# IMU_Radio.net
KiCad netlist of a schematic drawn in Altium Designer
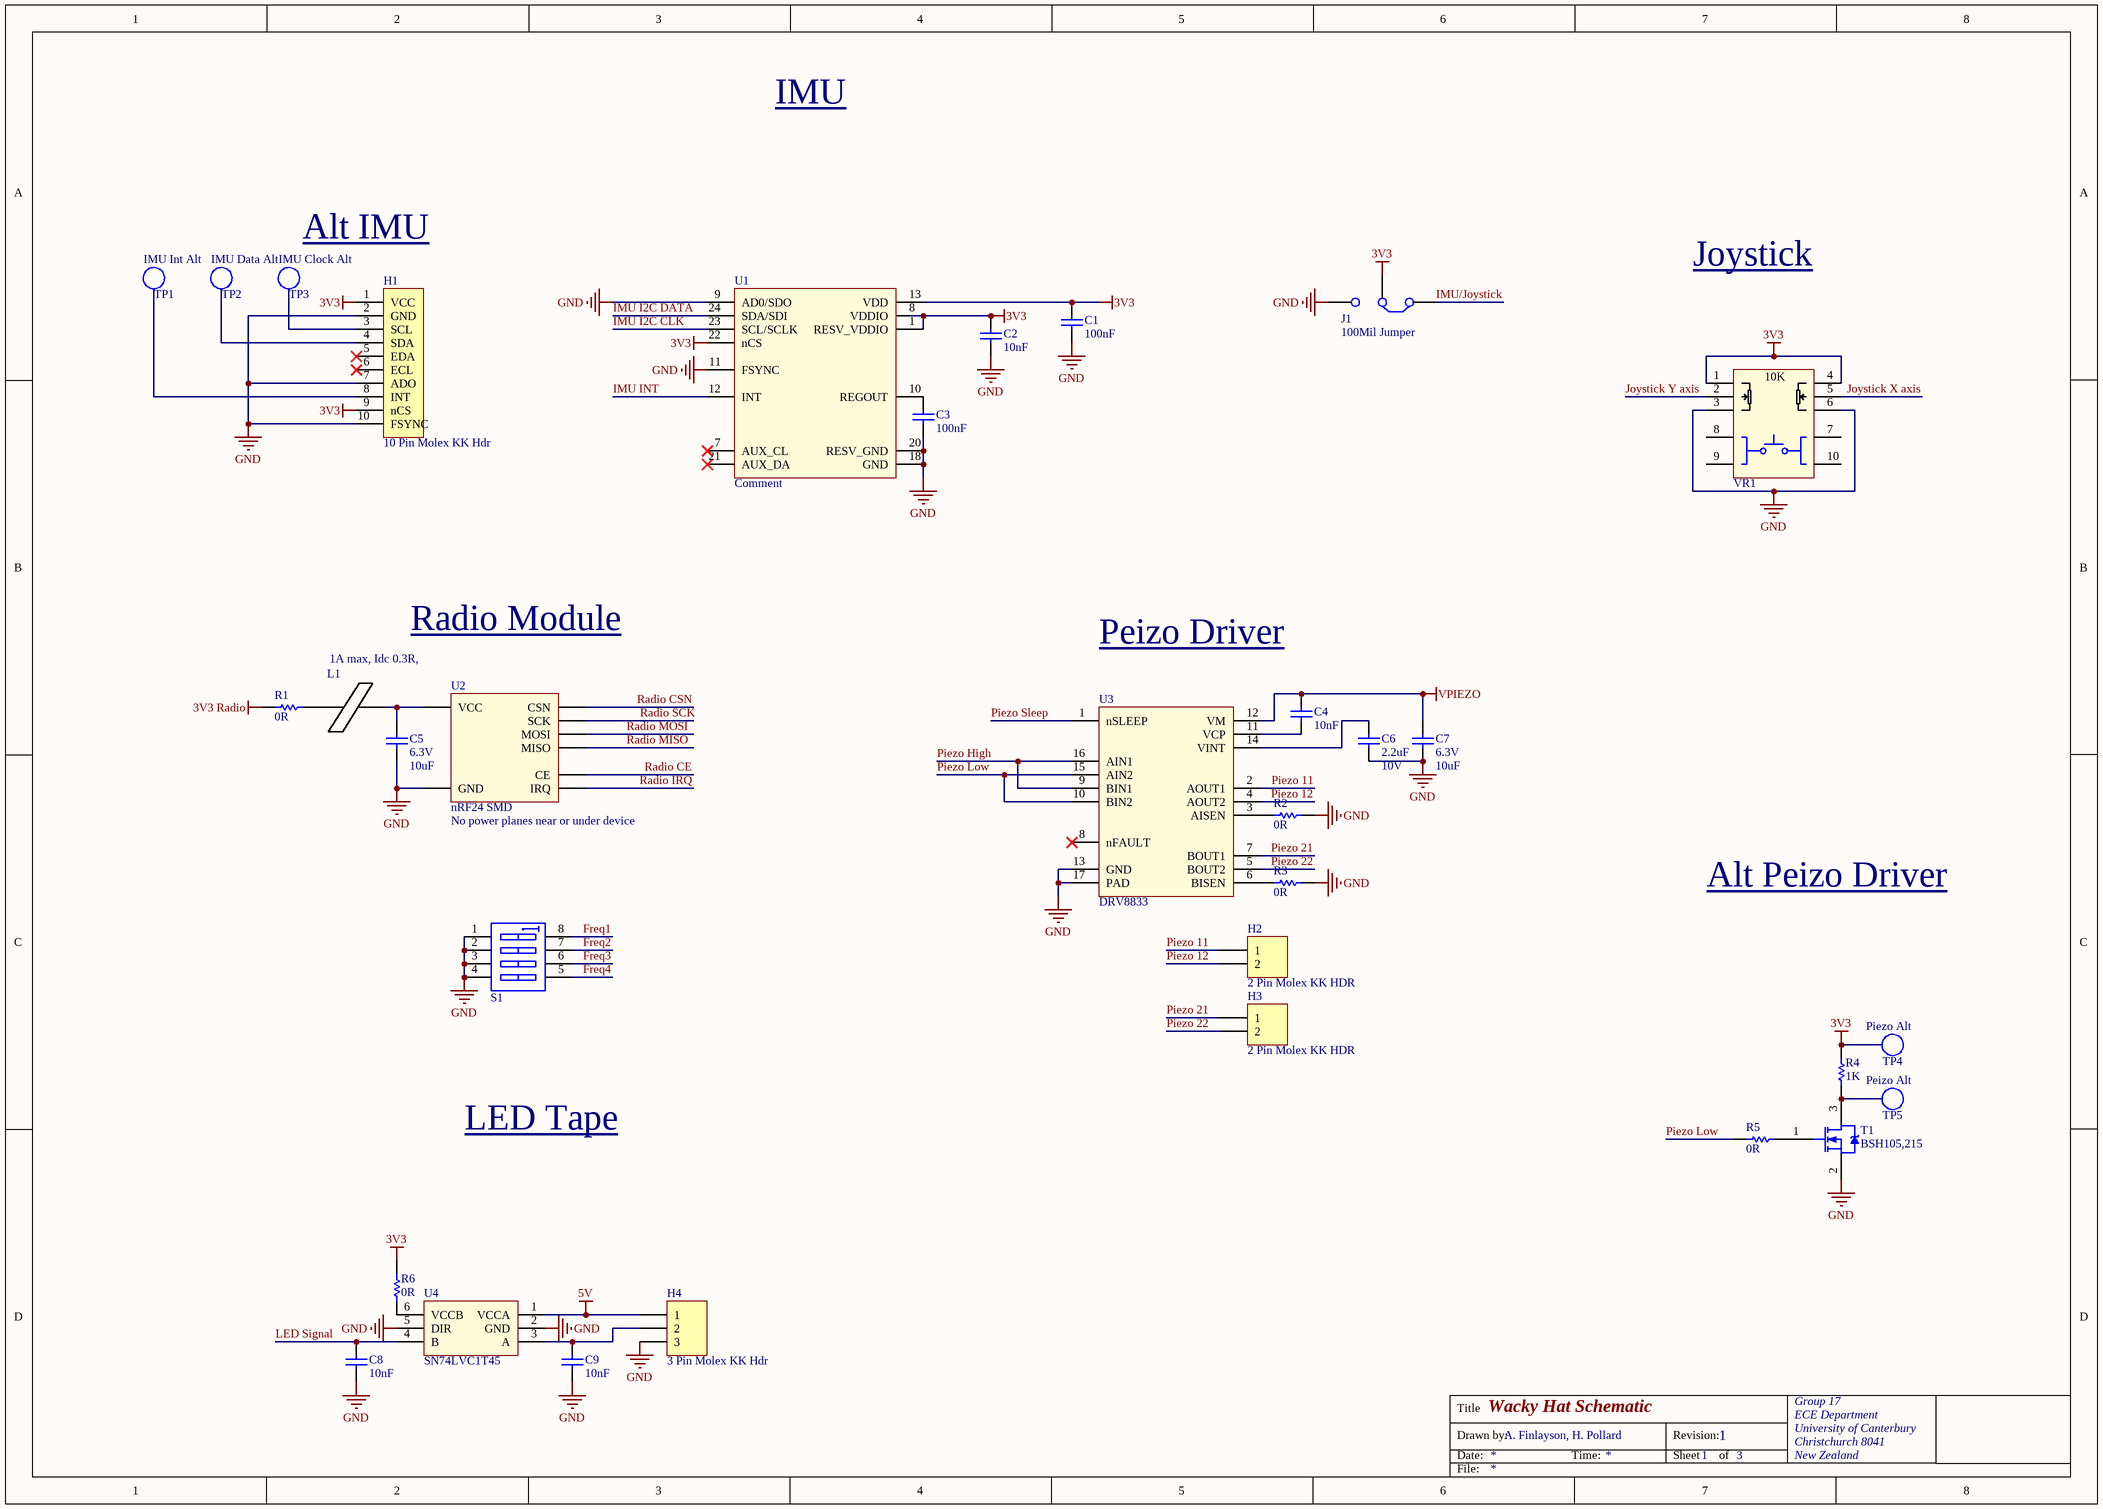
[diagram p0: IMU_Radio.SchDoc]

(export (version "E")
  (design (tool "Eeschema 10.0.6"))
  (components
    (comp (ref "C1")
      (value "100nF")
      (footprint "CAPC1608L")
      (description "CAP CER 100nF X7R +-10% 50V 0603")
      (libsource (lib "ECE AD19Components_19V1") (part "CC_100nF_0603"))
    )
    (comp (ref "C2")
      (value "10nF")
      (footprint "CAPC1608L")
      (description "CAP CER 10nF X7R +-10% 50V 0603")
      (libsource (lib "ECE AD19Components_19V1") (part "CC_10nF_0603"))
    )
    (comp (ref "C3")
      (value "100nF")
      (footprint "CAPC1608L")
      (description "CAP CER 100nF X7R +-10% 50V 0603")
      (libsource (lib "ECE AD19Components_19V1") (part "CC_100nF_0603"))
    )
    (comp (ref "C4")
      (value "10nF")
      (footprint "CAPC1608L")
      (description "CAP CER 10nF X7R +-10% 50V 0603")
      (libsource (lib "ECE AD19Components_19V1") (part "CC_10nF_0603"))
    )
    (comp (ref "C5")
      (value "10uF")
      (footprint "CAPC1608L")
      (description "CAP CER 10UF X5R +-20% 6V3 0603")
      (fields (field (name "VOLTAGE - RATED") "6.3V"))
      (libsource (lib "ECE AD19Components_19V1") (part "CC_10uF_0603"))
    )
    (comp (ref "C6")
      (value "2.2uF")
      (footprint "CAPC1608L")
      (description "CAP CER 2.2uF X5R +-20% 10V 0603")
      (fields (field (name "MAX VOLTAGE") "10V"))
      (libsource (lib "ECE AD19Components_19V1") (part "CC_2.2uF_0603"))
    )
    (comp (ref "C7")
      (value "10uF")
      (footprint "CAPC1608L")
      (description "CAP CER 10UF X5R +-20% 6V3 0603")
      (fields (field (name "VOLTAGE - RATED") "6.3V"))
      (libsource (lib "ECE AD19Components_19V1") (part "CC_10uF_0603"))
    )
    (comp (ref "C8")
      (value "10nF")
      (footprint "CAPC1608L")
      (description "CAP CER 10nF X7R +-10% 50V 0603")
      (libsource (lib "ECE AD19Components_19V1") (part "CC_10nF_0603"))
    )
    (comp (ref "C9")
      (value "10nF")
      (footprint "CAPC1608L")
      (description "CAP CER 10nF X7R +-10% 50V 0603")
      (libsource (lib "ECE AD19Components_19V1") (part "CC_10nF_0603"))
    )
    (comp (ref "H1")
      (value "10 Pin Molex KK Hdr")
      (footprint "MOLEX_KK_10_HDR")
      (description "CONN HEADER 10POS 2.54mm VERT_ Thru Hole")
      (libsource (lib "ECE AD19Components_19V1") (part "JA_MOLEX_KK_10POS"))
    )
    (comp (ref "H2")
      (value "2 Pin Molex KK HDR")
      (footprint "MOLEX_KK_2_HDR")
      (description "CONN HEADER 2POS 2.54mm VERT_Thru Hole")
      (libsource (lib "ECE AD19Components_19V1") (part "JA_MOLEX_KK_2POS"))
    )
    (comp (ref "H3")
      (value "2 Pin Molex KK HDR")
      (footprint "MOLEX_KK_2_HDR")
      (description "CONN HEADER 2POS 2.54mm VERT_Thru Hole")
      (libsource (lib "ECE AD19Components_19V1") (part "JA_MOLEX_KK_2POS"))
    )
    (comp (ref "H4")
      (value "3 Pin Molex KK Hdr")
      (footprint "MOLEX_KK_3_HDR")
      (description "CONN HEADER 3POS 2.54mm VERT_Thru Hole")
      (fields (field (name "MANUFACTURER") "Molex"))
      (libsource (lib "ECE AD19Components_19V1") (part "JA_MOLEX_KK_3POS"))
    )
    (comp (ref "J1")
      (value "100Mil Jumper")
      (footprint "JMP2.54-CO")
      (description "2.54mm Jumper change over, Thru Hole")
      (libsource (lib "ECE AD19Components_19V1") (part "TP_JUMPER_CO"))
    )
    (comp (ref "L1")
      (value "1A max, Idc 0.3R,")
      (footprint "INDC3216L")
      (description "Ferrite Bead, Rdc 0.3R, Z100MHZ 600R, Imax 1A, SMD 1206")
      (fields
        (field (name "MANUFACTURER") "FAIR-RITE")
        (field (name "MANUFACTURER PART NUMBER") "2512066017Y1")
      )
      (libsource (lib "ECE AD19Components_19V1") (part "IN_Ferrite-Bead"))
    )
    (comp (ref "R1")
      (value "0R")
      (footprint "RESC1608L")
      (description "RES 0.0 OHM 1/10W 5% 0603 SMD")
      (libsource (lib "ECE AD19Components_19V1") (part "RS_0R0"))
    )
    (comp (ref "R2")
      (value "0R")
      (footprint "RESC1608L")
      (description "RES 0.0 OHM 1/10W 5% 0603 SMD")
      (libsource (lib "ECE AD19Components_19V1") (part "RS_0R0"))
    )
    (comp (ref "R3")
      (value "0R")
      (footprint "RESC1608L")
      (description "RES 0.0 OHM 1/10W 5% 0603 SMD")
      (libsource (lib "ECE AD19Components_19V1") (part "RS_0R0"))
    )
    (comp (ref "R4")
      (value "1K")
      (footprint "RESC1608L")
      (description "RES 1.0K OHM 1/10W 5% 0603 SMD")
      (libsource (lib "ECE AD19Components_19V1") (part "RS_1K"))
    )
    (comp (ref "R5")
      (value "0R")
      (footprint "RESC1608L")
      (description "RES 0.0 OHM 1/10W 5% 0603 SMD")
      (libsource (lib "ECE AD19Components_19V1") (part "RS_0R0"))
    )
    (comp (ref "R6")
      (value "0R")
      (footprint "RESC1608L")
      (description "RES 0.0 OHM 1/10W 5% 0603 SMD")
      (libsource (lib "ECE AD19Components_19V1") (part "RS_0R0"))
    )
    (comp (ref "S1")
      (value "WS_SW DIP-4")
      (footprint "DIP_SW_4WAY_SMD -")
      (description "DIP Switch, 4 Position, SPST SMD")
      (fields
        (field (name "MANUFACTURER") "OMRON ELECTRONIC COMPONENTS")
        (field (name "MANUFACTURER PART NUMBER") "A6SN-4101")
      )
      (libsource (lib "ECE AD19Components_19V1") (part "WS_SW DIP-4"))
    )
    (comp (ref "T1")
      (value "BSH105,215")
      (footprint "SOT23_L")
      (description "MOSFET N-CH 20V 1.05A SOT-23")
      (fields
        (field (name "MANUFACTURER") "NXP Semiconductors")
        (field (name "MANUFACTURER PART NUMBER") "BSH105,215")
      )
      (libsource (lib "ECE AD19Components_19V1") (part "TM_BSH105"))
    )
    (comp (ref "TP1")
      (value "IMU Int Alt")
      (footprint "TP_0603")
      (description "Test Point 1.65X0.9X1.2mm SMD")
      (fields
        (field (name "MANUFACTURER") "TE Connectivity AMP Connectors")
        (field (name "MANUFACTURER PART NUMBER") "1625854-3")
      )
      (libsource (lib "ECE AD19Components_19V1") (part "TP_0603"))
    )
    (comp (ref "TP2")
      (value "IMU Data Alt")
      (footprint "TP_0603")
      (description "Test Point 1.65X0.9X1.2mm SMD")
      (fields
        (field (name "MANUFACTURER") "TE Connectivity AMP Connectors")
        (field (name "MANUFACTURER PART NUMBER") "1625854-3")
      )
      (libsource (lib "ECE AD19Components_19V1") (part "TP_0603"))
    )
    (comp (ref "TP3")
      (value "IMU Clock Alt")
      (footprint "TP_0603")
      (description "Test Point 1.65X0.9X1.2mm SMD")
      (fields
        (field (name "MANUFACTURER") "TE Connectivity AMP Connectors")
        (field (name "MANUFACTURER PART NUMBER") "1625854-3")
      )
      (libsource (lib "ECE AD19Components_19V1") (part "TP_0603"))
    )
    (comp (ref "TP4")
      (value "Piezo Alt")
      (footprint "TP_0603")
      (description "Test Point 1.65X0.9X1.2mm SMD")
      (fields
        (field (name "MANUFACTURER") "TE Connectivity AMP Connectors")
        (field (name "MANUFACTURER PART NUMBER") "1625854-3")
      )
      (libsource (lib "ECE AD19Components_19V1") (part "TP_0603"))
    )
    (comp (ref "TP5")
      (value "Peizo Alt")
      (footprint "TP_0603")
      (description "Test Point 1.65X0.9X1.2mm SMD")
      (fields
        (field (name "MANUFACTURER") "TE Connectivity AMP Connectors")
        (field (name "MANUFACTURER PART NUMBER") "1625854-3")
      )
      (libsource (lib "ECE AD19Components_19V1") (part "TP_0603"))
    )
    (comp (ref "U1")
      (value "Comment")
      (footprint "Quad24")
      (description "9 axis IMU")
      (libsource (lib "ENCE461AD19_19V2") (part "MPU-9250"))
    )
    (comp (ref "U2")
      (value "nRF24 SMD")
      (footprint "NRF24")
      (description "nRF24 SMD Module")
      (fields (field (name "WARNING") "No power planes near or under device"))
      (libsource (lib "ENCE461AD19_19V2") (part "NRF24"))
    )
    (comp (ref "U3")
      (value "DRV8833")
      (footprint "HTSOP16")
      (description "Dual H-Bridge Motor Driver 1.5A")
      (libsource (lib "ENCE461AD19_19V2") (part "DRV8833"))
    )
    (comp (ref "U4")
      (value "SN74LVC1T45")
      (footprint "SOT23-6_N")
      (description "1.8V - 5V level converter")
      (libsource (lib "ENCE461_extras_2020") (part "SN74LVC1T45"))
    )
    (comp (ref "VR1")
      (value "Joystick 10k with Sw")
      (footprint "Joystick_Sw")
      (description "JOYSTICK 10K OHM 2 AXIS TH")
      (libsource (lib "ENCE461AD19_19V2") (part "Joystick 10k with Sw"))
    )
  )
  (nets
    (net (code "1") (name "/Freq1") (class "Default")
      (node (ref "S1") (pin "8") (pinfunction "B1_8") (pintype "passive"))
    )
    (net (code "2") (name "/Freq2") (class "Default")
      (node (ref "S1") (pin "7") (pinfunction "B2_7") (pintype "passive"))
    )
    (net (code "3") (name "/Freq3") (class "Default")
      (node (ref "S1") (pin "6") (pinfunction "B3_6") (pintype "passive"))
    )
    (net (code "4") (name "/Freq4") (class "Default")
      (node (ref "S1") (pin "5") (pinfunction "B4_5") (pintype "passive"))
    )
    (net (code "5") (name "/IMU I2C CLK") (class "Default")
      (node (ref "U1") (pin "23") (pinfunction "SCL/SCLK_23") (pintype "passive"))
    )
    (net (code "6") (name "/IMU I2C DATA") (class "Default")
      (node (ref "U1") (pin "24") (pinfunction "SDA/SDI_24") (pintype "passive"))
    )
    (net (code "7") (name "/IMU INT") (class "Default")
      (node (ref "U1") (pin "12") (pinfunction "INT_12") (pintype "passive"))
    )
    (net (code "8") (name "/IMU{slash}Joystick") (class "Default")
      (node (ref "J1") (pin "1") (pinfunction "C1_1") (pintype "passive"))
    )
    (net (code "9") (name "/Joystick X axis") (class "Default")
      (node (ref "VR1") (pin "5") (pinfunction "2'_5") (pintype "passive"))
    )
    (net (code "10") (name "/Joystick Y axis") (class "Default")
      (node (ref "VR1") (pin "2") (pinfunction "2_2") (pintype "passive"))
    )
    (net (code "11") (name "/LED Signal") (class "Default")
      (node (ref "C8") (pin "2") (pinfunction "2_2") (pintype "passive"))
      (node (ref "U4") (pin "4") (pinfunction "B_4") (pintype "passive"))
    )
    (net (code "12") (name "/Piezo 11") (class "Default")
      (node (ref "H2") (pin "1") (pinfunction "1_1") (pintype "passive"))
      (node (ref "U3") (pin "2") (pinfunction "AOUT1_2") (pintype "passive"))
    )
    (net (code "13") (name "/Piezo 12") (class "Default")
      (node (ref "H2") (pin "2") (pinfunction "2_2") (pintype "passive"))
      (node (ref "U3") (pin "4") (pinfunction "AOUT2_4") (pintype "passive"))
    )
    (net (code "14") (name "/Piezo 21") (class "Default")
      (node (ref "H3") (pin "1") (pinfunction "1_1") (pintype "passive"))
      (node (ref "U3") (pin "7") (pinfunction "BOUT1_7") (pintype "passive"))
    )
    (net (code "15") (name "/Piezo 22") (class "Default")
      (node (ref "H3") (pin "2") (pinfunction "2_2") (pintype "passive"))
      (node (ref "U3") (pin "5") (pinfunction "BOUT2_5") (pintype "passive"))
    )
    (net (code "16") (name "/Piezo High") (class "Default")
      (node (ref "U3") (pin "16") (pinfunction "AIN1_16") (pintype "passive"))
      (node (ref "U3") (pin "9") (pinfunction "BIN1_9") (pintype "passive"))
    )
    (net (code "17") (name "/Piezo Low") (class "Default")
      (node (ref "R5") (pin "1") (pinfunction "1_1") (pintype "passive"))
      (node (ref "U3") (pin "10") (pinfunction "BIN2_10") (pintype "passive"))
      (node (ref "U3") (pin "15") (pinfunction "AIN2_15") (pintype "passive"))
    )
    (net (code "18") (name "/Piezo Sleep") (class "Default")
      (node (ref "U3") (pin "1") (pinfunction "nSLEEP_1") (pintype "passive"))
    )
    (net (code "19") (name "/Radio CE") (class "Default")
      (node (ref "U2") (pin "3") (pinfunction "CE_3") (pintype "passive"))
    )
    (net (code "20") (name "/Radio CSN") (class "Default")
      (node (ref "U2") (pin "4") (pinfunction "CSN_4") (pintype "passive"))
    )
    (net (code "21") (name "/Radio IRQ") (class "Default")
      (node (ref "U2") (pin "8") (pinfunction "IRQ_8") (pintype "passive"))
    )
    (net (code "22") (name "/Radio MISO") (class "Default")
      (node (ref "U2") (pin "7") (pinfunction "MISO_7") (pintype "passive"))
    )
    (net (code "23") (name "/Radio MOSI") (class "Default")
      (node (ref "U2") (pin "6") (pinfunction "MOSI_6") (pintype "passive"))
    )
    (net (code "24") (name "/Radio SCK") (class "Default")
      (node (ref "U2") (pin "5") (pinfunction "SCK_5") (pintype "passive"))
    )
    (net (code "25") (name "3V3") (class "Default")
      (node (ref "C1") (pin "2") (pinfunction "2_2") (pintype "passive"))
      (node (ref "C2") (pin "2") (pinfunction "2_2") (pintype "passive"))
      (node (ref "H1") (pin "1") (pinfunction "VCC_1") (pintype "passive"))
      (node (ref "H1") (pin "9") (pinfunction "nCS_9") (pintype "passive"))
      (node (ref "J1") (pin "2") (pinfunction "C2_2") (pintype "passive"))
      (node (ref "R4") (pin "2") (pinfunction "2_2") (pintype "passive"))
      (node (ref "R6") (pin "2") (pinfunction "2_2") (pintype "passive"))
      (node (ref "TP4") (pin "1") (pinfunction "TP_1") (pintype "passive"))
      (node (ref "U1") (pin "1") (pinfunction "RESV_VDDIO_1") (pintype "passive"))
      (node (ref "U1") (pin "13") (pinfunction "VDD_13") (pintype "passive"))
      (node (ref "U1") (pin "22") (pinfunction "nCS_22") (pintype "passive"))
      (node (ref "U1") (pin "8") (pinfunction "VDDIO_8") (pintype "passive"))
      (node (ref "VR1") (pin "1") (pinfunction "1_1") (pintype "passive"))
      (node (ref "VR1") (pin "4") (pinfunction "1'_4") (pintype "passive"))
    )
    (net (code "26") (name "3V3 Radio") (class "Default")
      (node (ref "R1") (pin "1") (pinfunction "1_1") (pintype "passive"))
    )
    (net (code "27") (name "5V") (class "Default")
      (node (ref "H4") (pin "1") (pinfunction "1_1") (pintype "passive"))
      (node (ref "U4") (pin "1") (pinfunction "VCCA_1") (pintype "passive"))
    )
    (net (code "28") (name "GND") (class "Default")
      (node (ref "C1") (pin "1") (pinfunction "1_1") (pintype "passive"))
      (node (ref "C2") (pin "1") (pinfunction "1_1") (pintype "passive"))
      (node (ref "C3") (pin "1") (pinfunction "1_1") (pintype "passive"))
      (node (ref "C5") (pin "1") (pinfunction "1_1") (pintype "passive"))
      (node (ref "C6") (pin "2") (pinfunction "2_2") (pintype "passive"))
      (node (ref "C7") (pin "1") (pinfunction "1_1") (pintype "passive"))
      (node (ref "C8") (pin "1") (pinfunction "1_1") (pintype "passive"))
      (node (ref "C9") (pin "1") (pinfunction "1_1") (pintype "passive"))
      (node (ref "H1") (pin "10") (pinfunction "FSYNC_10") (pintype "passive"))
      (node (ref "H1") (pin "2") (pinfunction "GND_2") (pintype "passive"))
      (node (ref "H1") (pin "7") (pinfunction "ADO_7") (pintype "passive"))
      (node (ref "H4") (pin "3") (pinfunction "3_3") (pintype "passive"))
      (node (ref "J1") (pin "3") (pinfunction "C3_3") (pintype "passive"))
      (node (ref "R2") (pin "2") (pinfunction "2_2") (pintype "passive"))
      (node (ref "R3") (pin "2") (pinfunction "2_2") (pintype "passive"))
      (node (ref "S1") (pin "1") (pinfunction "A1_1") (pintype "passive"))
      (node (ref "S1") (pin "2") (pinfunction "A2_2") (pintype "passive"))
      (node (ref "S1") (pin "3") (pinfunction "A3_3") (pintype "passive"))
      (node (ref "S1") (pin "4") (pinfunction "A4_4") (pintype "passive"))
      (node (ref "T1") (pin "2") (pinfunction "2_2") (pintype "passive"))
      (node (ref "U1") (pin "11") (pinfunction "FSYNC_11") (pintype "passive"))
      (node (ref "U1") (pin "18") (pinfunction "GND_18") (pintype "passive"))
      (node (ref "U1") (pin "20") (pinfunction "RESV_GND_20") (pintype "passive"))
      (node (ref "U1") (pin "9") (pinfunction "AD0/SDO_9") (pintype "passive"))
      (node (ref "U2") (pin "2") (pinfunction "GND_2") (pintype "passive"))
      (node (ref "U3") (pin "13") (pinfunction "GND_13") (pintype "passive"))
      (node (ref "U3") (pin "17") (pinfunction "PAD_17") (pintype "passive"))
      (node (ref "U4") (pin "2") (pinfunction "GND_2") (pintype "passive"))
      (node (ref "U4") (pin "5") (pinfunction "DIR_5") (pintype "passive"))
      (node (ref "VR1") (pin "3") (pinfunction "3_3") (pintype "passive"))
      (node (ref "VR1") (pin "6") (pinfunction "3'_6") (pintype "passive"))
    )
    (net (code "29") (name "Net-(H1-INT)") (class "Default")
      (node (ref "H1") (pin "8") (pinfunction "INT_8") (pintype "passive"))
      (node (ref "TP1") (pin "1") (pinfunction "TP_1") (pintype "passive"))
    )
    (net (code "30") (name "Net-(H1-SCL)") (class "Default")
      (node (ref "H1") (pin "3") (pinfunction "SCL_3") (pintype "passive"))
      (node (ref "TP3") (pin "1") (pinfunction "TP_1") (pintype "passive"))
    )
    (net (code "31") (name "Net-(H1-SDA)") (class "Default")
      (node (ref "H1") (pin "4") (pinfunction "SDA_4") (pintype "passive"))
      (node (ref "TP2") (pin "1") (pinfunction "TP_1") (pintype "passive"))
    )
    (net (code "32") (name "Net-(L1-Pad2)") (class "Default")
      (node (ref "L1") (pin "2") (pinfunction "2_2") (pintype "passive"))
      (node (ref "R1") (pin "2") (pinfunction "2_2") (pintype "passive"))
    )
    (net (code "33") (name "Net-(R5-Pad2)") (class "Default")
      (node (ref "R5") (pin "2") (pinfunction "2_2") (pintype "passive"))
      (node (ref "T1") (pin "1") (pinfunction "1_1") (pintype "passive"))
    )
    (net (code "34") (name "Net-(TP5-TP)") (class "Default")
      (node (ref "R4") (pin "1") (pinfunction "1_1") (pintype "passive"))
      (node (ref "T1") (pin "3") (pinfunction "3_3") (pintype "passive"))
      (node (ref "TP5") (pin "1") (pinfunction "TP_1") (pintype "passive"))
    )
    (net (code "35") (name "Net-(U1-REGOUT)") (class "Default")
      (node (ref "C3") (pin "2") (pinfunction "2_2") (pintype "passive"))
      (node (ref "U1") (pin "10") (pinfunction "REGOUT_10") (pintype "passive"))
    )
    (net (code "36") (name "Net-(U2-VCC)") (class "Default")
      (node (ref "C5") (pin "2") (pinfunction "2_2") (pintype "passive"))
      (node (ref "L1") (pin "1") (pinfunction "1_1") (pintype "passive"))
      (node (ref "U2") (pin "1") (pinfunction "VCC_1") (pintype "passive"))
    )
    (net (code "37") (name "Net-(U3-AISEN)") (class "Default")
      (node (ref "R2") (pin "1") (pinfunction "1_1") (pintype "passive"))
      (node (ref "U3") (pin "3") (pinfunction "AISEN_3") (pintype "passive"))
    )
    (net (code "38") (name "Net-(U3-BISEN)") (class "Default")
      (node (ref "R3") (pin "1") (pinfunction "1_1") (pintype "passive"))
      (node (ref "U3") (pin "6") (pinfunction "BISEN_6") (pintype "passive"))
    )
    (net (code "39") (name "Net-(U3-VCP)") (class "Default")
      (node (ref "C4") (pin "1") (pinfunction "1_1") (pintype "passive"))
      (node (ref "U3") (pin "11") (pinfunction "VCP_11") (pintype "passive"))
    )
    (net (code "40") (name "Net-(U3-VINT)") (class "Default")
      (node (ref "C6") (pin "1") (pinfunction "1_1") (pintype "passive"))
      (node (ref "U3") (pin "14") (pinfunction "VINT_14") (pintype "passive"))
    )
    (net (code "41") (name "Net-(U4-A)") (class "Default")
      (node (ref "C9") (pin "2") (pinfunction "2_2") (pintype "passive"))
      (node (ref "H4") (pin "2") (pinfunction "2_2") (pintype "passive"))
      (node (ref "U4") (pin "3") (pinfunction "A_3") (pintype "passive"))
    )
    (net (code "42") (name "Net-(U4-VCCB)") (class "Default")
      (node (ref "R6") (pin "1") (pinfunction "1_1") (pintype "passive"))
      (node (ref "U4") (pin "6") (pinfunction "VCCB_6") (pintype "passive"))
    )
    (net (code "43") (name "VPIEZO") (class "Default")
      (node (ref "C4") (pin "2") (pinfunction "2_2") (pintype "passive"))
      (node (ref "C7") (pin "2") (pinfunction "2_2") (pintype "passive"))
      (node (ref "U3") (pin "12") (pinfunction "VM_12") (pintype "passive"))
    )
    (net (code "44") (name "unconnected-(H1-ECL-Pad6)") (class "Default")
      (node (ref "H1") (pin "6") (pinfunction "ECL_6") (pintype "passive+no_connect"))
    )
    (net (code "45") (name "unconnected-(H1-EDA-Pad5)") (class "Default")
      (node (ref "H1") (pin "5") (pinfunction "EDA_5") (pintype "passive+no_connect"))
    )
    (net (code "46") (name "unconnected-(U1-AUX_CL-Pad7)") (class "Default")
      (node (ref "U1") (pin "7") (pinfunction "AUX_CL_7") (pintype "passive+no_connect"))
    )
    (net (code "47") (name "unconnected-(U1-AUX_DA-Pad21)") (class "Default")
      (node (ref "U1") (pin "21") (pinfunction "AUX_DA_21") (pintype "passive+no_connect"))
    )
    (net (code "48") (name "unconnected-(U3-nFAULT-Pad8)") (class "Default")
      (node (ref "U3") (pin "8") (pinfunction "nFAULT_8") (pintype "passive+no_connect"))
    )
    (net (code "49") (name "unconnected-(VR1-Pad7)") (class "Default")
      (node (ref "VR1") (pin "7") (pinfunction "7_7") (pintype "passive"))
    )
    (net (code "50") (name "unconnected-(VR1-Pad8)") (class "Default")
      (node (ref "VR1") (pin "8") (pinfunction "8_8") (pintype "passive"))
    )
    (net (code "51") (name "unconnected-(VR1-Pad9)") (class "Default")
      (node (ref "VR1") (pin "9") (pinfunction "9_9") (pintype "passive"))
    )
    (net (code "52") (name "unconnected-(VR1-Pad10)") (class "Default")
      (node (ref "VR1") (pin "10") (pinfunction "10_10") (pintype "passive"))
    )
  )
)
